# Digital.net
KiCad netlist of a schematic drawn in Altium Designer
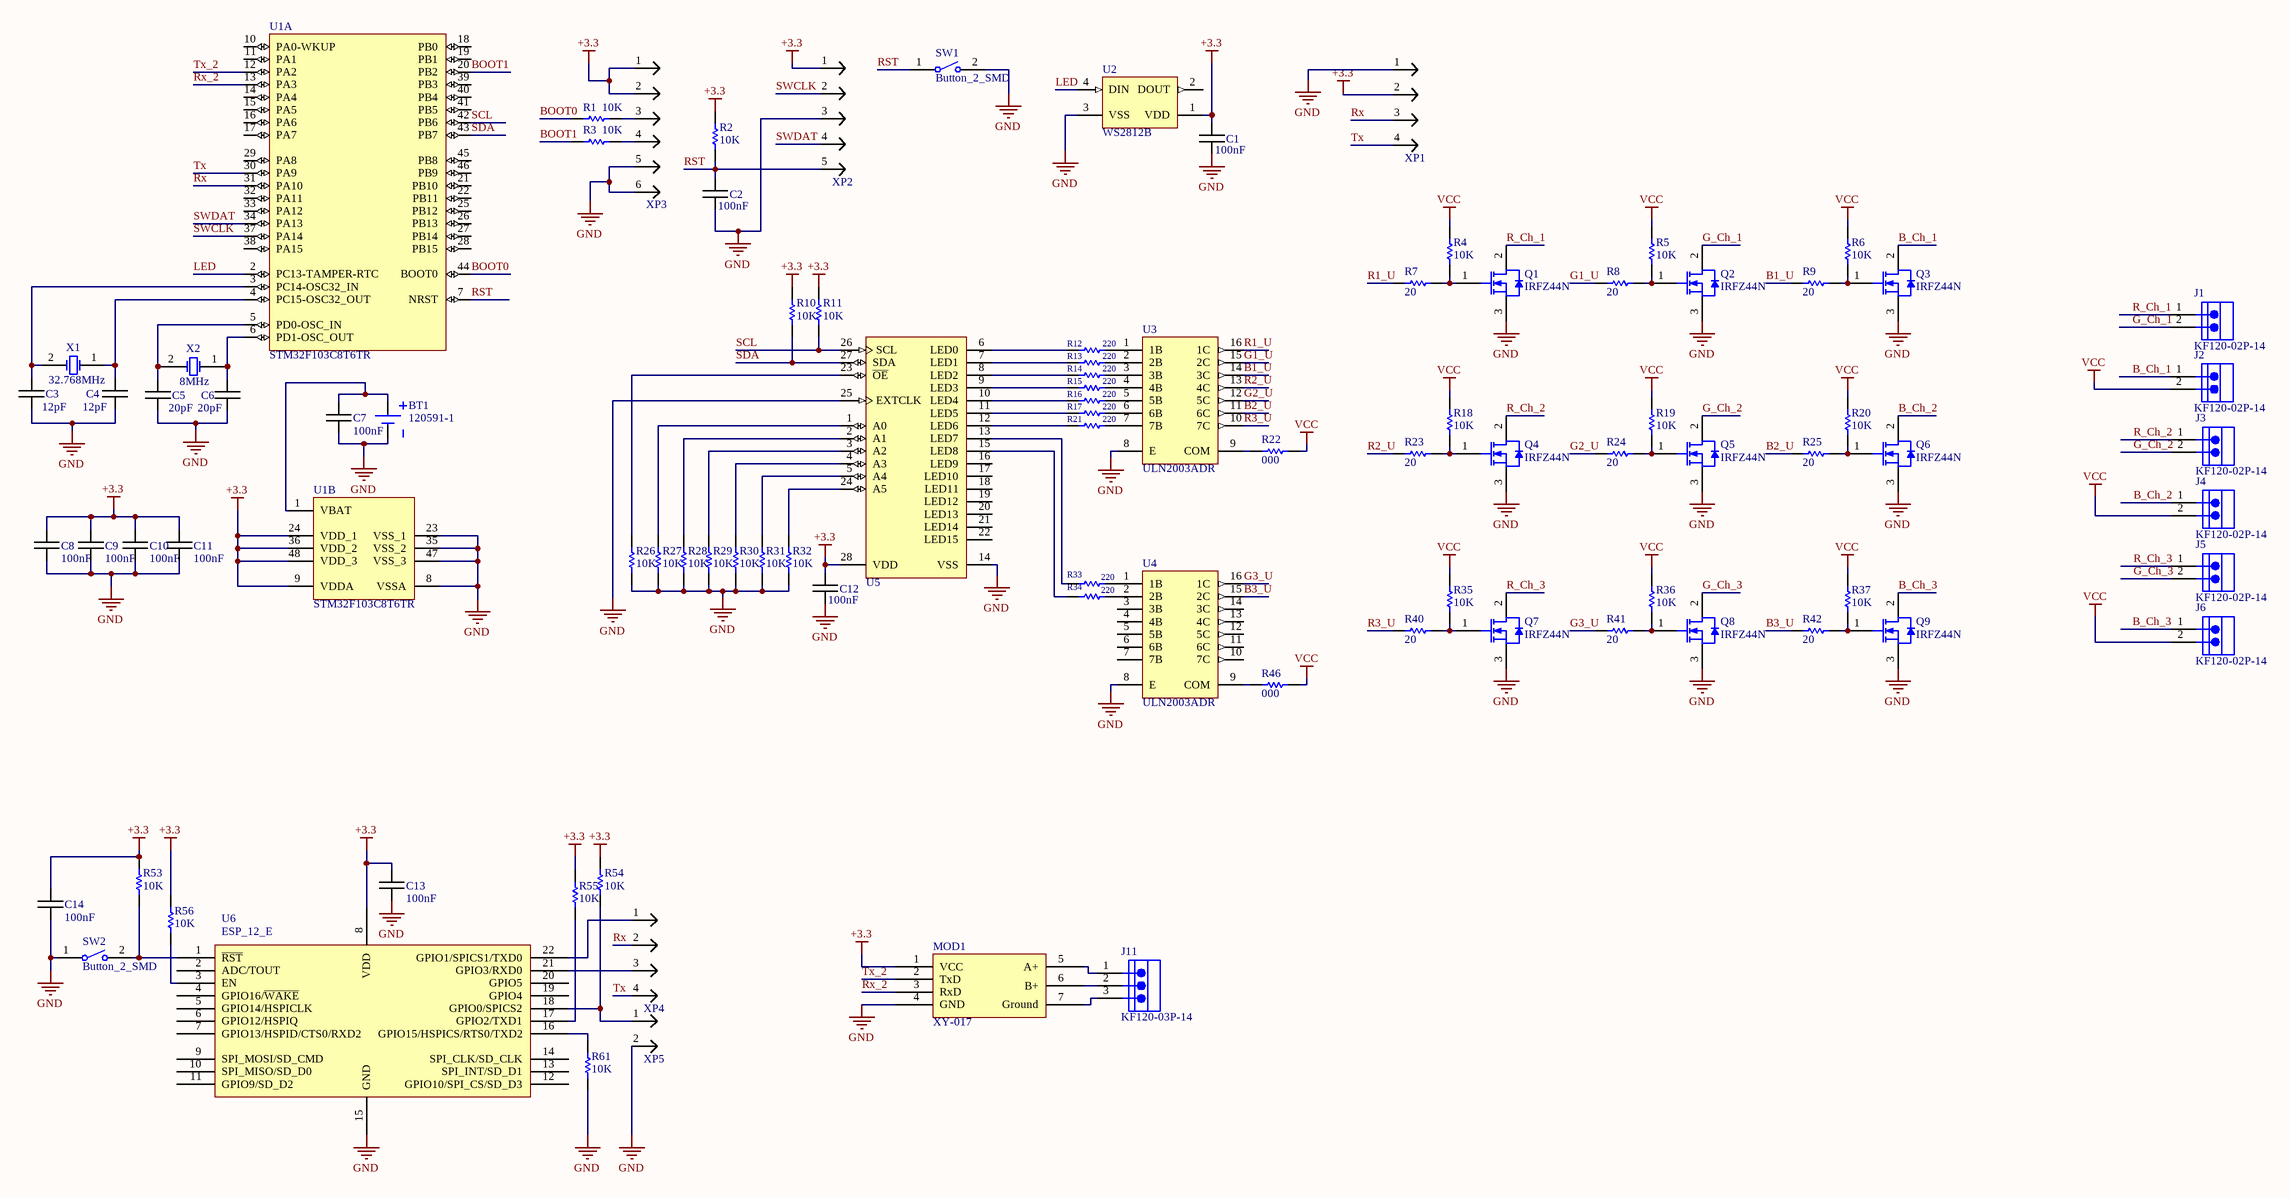
[diagram p0: Digital.SchDoc]

(export (version "E")
  (design (tool "Eeschema 10.0.6"))
  (components
    (comp (ref "BT1")
      (value "120591-1")
      (footprint "TECO-120591-1-2_V")
      (description "Lithium Battery Holder for CR2032 3V Cell")
      (fields (field (name "MANUFACTURER") "TE Connectivity"))
      (libsource (lib "altium-import") (part "root_3_CR-2032_"))
    )
    (comp (ref "C1")
      (value "CAP_SMD")
      (footprint "CAP0805")
      (description "Ceramic capacitor, 0805")
      (fields (field (name "VAL") "100nF"))
      (libsource (lib "altium-import") (part "root_1_CAP_SMD_"))
    )
    (comp (ref "C2")
      (value "CAP_SMD")
      (footprint "CAP0805")
      (description "Ceramic capacitor, 0805")
      (fields (field (name "VAL") "100nF"))
      (libsource (lib "altium-import") (part "root_1_CAP_SMD_"))
    )
    (comp (ref "C3")
      (value "CAP_SMD")
      (footprint "CAP0805")
      (description "Ceramic capacitor, 0805")
      (fields (field (name "VAL") "12pF"))
      (libsource (lib "altium-import") (part "root_1_CAP_SMD_"))
    )
    (comp (ref "C4")
      (value "CAP_SMD")
      (footprint "CAP0805")
      (description "Ceramic capacitor, 0805")
      (fields (field (name "VAL") "12pF"))
      (libsource (lib "altium-import") (part "root_1_CAP_SMD_"))
    )
    (comp (ref "C5")
      (value "CAP_SMD")
      (footprint "CAP0805")
      (description "Ceramic capacitor, 0805")
      (fields (field (name "VAL") "20pF"))
      (libsource (lib "altium-import") (part "root_1_CAP_SMD_"))
    )
    (comp (ref "C6")
      (value "CAP_SMD")
      (footprint "CAP0805")
      (description "Ceramic capacitor, 0805")
      (fields (field (name "VAL") "20pF"))
      (libsource (lib "altium-import") (part "root_1_CAP_SMD_"))
    )
    (comp (ref "C7")
      (value "CAP_SMD")
      (footprint "CAP0805")
      (description "Ceramic capacitor, 0805")
      (fields (field (name "VAL") "100nF"))
      (libsource (lib "altium-import") (part "root_1_CAP_SMD_"))
    )
    (comp (ref "C8")
      (value "CAP_SMD")
      (footprint "CAP0805")
      (description "Ceramic capacitor, 0805")
      (fields (field (name "VAL") "100nF"))
      (libsource (lib "altium-import") (part "root_1_CAP_SMD_"))
    )
    (comp (ref "C9")
      (value "CAP_SMD")
      (footprint "CAP0805")
      (description "Ceramic capacitor, 0805")
      (fields (field (name "VAL") "100nF"))
      (libsource (lib "altium-import") (part "root_1_CAP_SMD_"))
    )
    (comp (ref "C10")
      (value "CAP_SMD")
      (footprint "CAP0805")
      (description "Ceramic capacitor, 0805")
      (fields (field (name "VAL") "100nF"))
      (libsource (lib "altium-import") (part "root_1_CAP_SMD_"))
    )
    (comp (ref "C11")
      (value "CAP_SMD")
      (footprint "CAP0805")
      (description "Ceramic capacitor, 0805")
      (fields (field (name "VAL") "100nF"))
      (libsource (lib "altium-import") (part "root_1_CAP_SMD_"))
    )
    (comp (ref "C12")
      (value "CAP_SMD")
      (footprint "CAP0805")
      (description "Ceramic capacitor, 0805")
      (fields (field (name "VAL") "100nF"))
      (libsource (lib "altium-import") (part "root_1_CAP_SMD_"))
    )
    (comp (ref "C13")
      (value "CAP_SMD")
      (footprint "CAP0805")
      (description "Ceramic capacitor, 0805")
      (fields (field (name "VAL") "100nF"))
      (libsource (lib "altium-import") (part "root_1_CAP_SMD_"))
    )
    (comp (ref "C14")
      (value "CAP_SMD")
      (footprint "CAP0805")
      (description "Ceramic capacitor, 0805")
      (fields (field (name "VAL") "100nF"))
      (libsource (lib "altium-import") (part "root_1_CAP_SMD_"))
    )
    (comp (ref "J1")
      (value "KF120-02P-14")
      (footprint "KF350-3.5-02P")
      (fields (field (name "MANUFACTURER") "Cixi KaiFeng") (field (name "CONTACT") "Brass"))
      (libsource (lib "altium-import") (part "root_3_Terminal_2_"))
    )
    (comp (ref "J2")
      (value "KF120-02P-14")
      (footprint "KF350-3.5-02P")
      (fields (field (name "MANUFACTURER") "Cixi KaiFeng") (field (name "CONTACT") "Brass"))
      (libsource (lib "altium-import") (part "root_3_Terminal_2_"))
    )
    (comp (ref "J3")
      (value "KF120-02P-14")
      (footprint "KF350-3.5-02P")
      (fields (field (name "MANUFACTURER") "Cixi KaiFeng") (field (name "CONTACT") "Brass"))
      (libsource (lib "altium-import") (part "root_3_Terminal_2_"))
    )
    (comp (ref "J4")
      (value "KF120-02P-14")
      (footprint "KF350-3.5-02P")
      (fields (field (name "MANUFACTURER") "Cixi KaiFeng") (field (name "CONTACT") "Brass"))
      (libsource (lib "altium-import") (part "root_3_Terminal_2_"))
    )
    (comp (ref "J5")
      (value "KF120-02P-14")
      (footprint "KF350-3.5-02P")
      (fields (field (name "MANUFACTURER") "Cixi KaiFeng") (field (name "CONTACT") "Brass"))
      (libsource (lib "altium-import") (part "root_3_Terminal_2_"))
    )
    (comp (ref "J6")
      (value "KF120-02P-14")
      (footprint "KF350-3.5-02P")
      (fields (field (name "MANUFACTURER") "Cixi KaiFeng") (field (name "CONTACT") "Brass"))
      (libsource (lib "altium-import") (part "root_3_Terminal_2_"))
    )
    (comp (ref "J11")
      (value "KF120-03P-14")
      (footprint "KF350-3.5-03P")
      (fields (field (name "MANUFACTURER") "Cixi KaiFeng") (field (name "CONTACT") "Brass"))
      (libsource (lib "altium-import") (part "root_3_Terminal_3_"))
    )
    (comp (ref "MOD1")
      (value "XY-017")
      (footprint "XY-017")
      (description "XY-017 RS-485 to ttl module")
      (libsource (lib "altium-import") (part "root_0_XY-017_"))
    )
    (comp (ref "Q1")
      (value "IRFZ44N")
      (footprint "TO-220")
      (description "N-channel Enhancement Mode Power MOSFET 49A/55V")
      (libsource (lib "altium-import") (part "root_0_IRFZ44N_"))
    )
    (comp (ref "Q2")
      (value "IRFZ44N")
      (footprint "TO-220")
      (description "N-channel Enhancement Mode Power MOSFET 49A/55V")
      (libsource (lib "altium-import") (part "root_0_IRFZ44N_"))
    )
    (comp (ref "Q3")
      (value "IRFZ44N")
      (footprint "TO-220")
      (description "N-channel Enhancement Mode Power MOSFET 49A/55V")
      (libsource (lib "altium-import") (part "root_0_IRFZ44N_"))
    )
    (comp (ref "Q4")
      (value "IRFZ44N")
      (footprint "TO-220")
      (description "N-channel Enhancement Mode Power MOSFET 49A/55V")
      (libsource (lib "altium-import") (part "root_0_IRFZ44N_"))
    )
    (comp (ref "Q5")
      (value "IRFZ44N")
      (footprint "TO-220")
      (description "N-channel Enhancement Mode Power MOSFET 49A/55V")
      (libsource (lib "altium-import") (part "root_0_IRFZ44N_"))
    )
    (comp (ref "Q6")
      (value "IRFZ44N")
      (footprint "TO-220")
      (description "N-channel Enhancement Mode Power MOSFET 49A/55V")
      (libsource (lib "altium-import") (part "root_0_IRFZ44N_"))
    )
    (comp (ref "Q7")
      (value "IRFZ44N")
      (footprint "TO-220")
      (description "N-channel Enhancement Mode Power MOSFET 49A/55V")
      (libsource (lib "altium-import") (part "root_0_IRFZ44N_"))
    )
    (comp (ref "Q8")
      (value "IRFZ44N")
      (footprint "TO-220")
      (description "N-channel Enhancement Mode Power MOSFET 49A/55V")
      (libsource (lib "altium-import") (part "root_0_IRFZ44N_"))
    )
    (comp (ref "Q9")
      (value "IRFZ44N")
      (footprint "TO-220")
      (description "N-channel Enhancement Mode Power MOSFET 49A/55V")
      (libsource (lib "altium-import") (part "root_0_IRFZ44N_"))
    )
    (comp (ref "R1")
      (value "RES_SMD")
      (footprint "RES0805")
      (fields (field (name "VAL") "10K"))
      (libsource (lib "altium-import") (part "root_0_RES_SMD_"))
    )
    (comp (ref "R2")
      (value "RES_SMD")
      (footprint "RES0805")
      (fields (field (name "VAL") "10K"))
      (libsource (lib "altium-import") (part "root_1_RES_SMD_"))
    )
    (comp (ref "R3")
      (value "RES_SMD")
      (footprint "RES0805")
      (fields (field (name "VAL") "10K"))
      (libsource (lib "altium-import") (part "root_0_RES_SMD_"))
    )
    (comp (ref "R4")
      (value "RES_SMD")
      (footprint "RES0805")
      (fields (field (name "VAL") "10K"))
      (libsource (lib "altium-import") (part "root_1_RES_SMD_"))
    )
    (comp (ref "R5")
      (value "RES_SMD")
      (footprint "RES0805")
      (fields (field (name "VAL") "10K"))
      (libsource (lib "altium-import") (part "root_1_RES_SMD_"))
    )
    (comp (ref "R6")
      (value "RES_SMD")
      (footprint "RES0805")
      (fields (field (name "VAL") "10K"))
      (libsource (lib "altium-import") (part "root_1_RES_SMD_"))
    )
    (comp (ref "R7")
      (value "RES_SMD")
      (footprint "RES0805")
      (fields (field (name "VAL") "20"))
      (libsource (lib "altium-import") (part "root_0_RES_SMD_"))
    )
    (comp (ref "R8")
      (value "RES_SMD")
      (footprint "RES0805")
      (fields (field (name "VAL") "20"))
      (libsource (lib "altium-import") (part "root_0_RES_SMD_"))
    )
    (comp (ref "R9")
      (value "RES_SMD")
      (footprint "RES0805")
      (fields (field (name "VAL") "20"))
      (libsource (lib "altium-import") (part "root_0_RES_SMD_"))
    )
    (comp (ref "R10")
      (value "RES_SMD")
      (footprint "RES0805")
      (fields (field (name "VAL") "10K"))
      (libsource (lib "altium-import") (part "root_1_RES_SMD_"))
    )
    (comp (ref "R11")
      (value "RES_SMD")
      (footprint "RES0805")
      (fields (field (name "VAL") "10K"))
      (libsource (lib "altium-import") (part "root_1_RES_SMD_"))
    )
    (comp (ref "R12")
      (value "RES_SMD")
      (footprint "RES0805")
      (fields (field (name "VAL") "220"))
      (libsource (lib "altium-import") (part "root_2_RES_SMD_"))
    )
    (comp (ref "R13")
      (value "RES_SMD")
      (footprint "RES0805")
      (fields (field (name "VAL") "220"))
      (libsource (lib "altium-import") (part "root_2_RES_SMD_"))
    )
    (comp (ref "R14")
      (value "RES_SMD")
      (footprint "RES0805")
      (fields (field (name "VAL") "220"))
      (libsource (lib "altium-import") (part "root_2_RES_SMD_"))
    )
    (comp (ref "R15")
      (value "RES_SMD")
      (footprint "RES0805")
      (fields (field (name "VAL") "220"))
      (libsource (lib "altium-import") (part "root_2_RES_SMD_"))
    )
    (comp (ref "R16")
      (value "RES_SMD")
      (footprint "RES0805")
      (fields (field (name "VAL") "220"))
      (libsource (lib "altium-import") (part "root_2_RES_SMD_"))
    )
    (comp (ref "R17")
      (value "RES_SMD")
      (footprint "RES0805")
      (fields (field (name "VAL") "220"))
      (libsource (lib "altium-import") (part "root_2_RES_SMD_"))
    )
    (comp (ref "R18")
      (value "RES_SMD")
      (footprint "RES0805")
      (fields (field (name "VAL") "10K"))
      (libsource (lib "altium-import") (part "root_1_RES_SMD_"))
    )
    (comp (ref "R19")
      (value "RES_SMD")
      (footprint "RES0805")
      (fields (field (name "VAL") "10K"))
      (libsource (lib "altium-import") (part "root_1_RES_SMD_"))
    )
    (comp (ref "R20")
      (value "RES_SMD")
      (footprint "RES0805")
      (fields (field (name "VAL") "10K"))
      (libsource (lib "altium-import") (part "root_1_RES_SMD_"))
    )
    (comp (ref "R21")
      (value "RES_SMD")
      (footprint "RES0805")
      (fields (field (name "VAL") "220"))
      (libsource (lib "altium-import") (part "root_2_RES_SMD_"))
    )
    (comp (ref "R22")
      (value "RES_SMD")
      (footprint "RES0805")
      (fields (field (name "VAL") "000"))
      (libsource (lib "altium-import") (part "root_0_RES_SMD_"))
    )
    (comp (ref "R23")
      (value "RES_SMD")
      (footprint "RES0805")
      (fields (field (name "VAL") "20"))
      (libsource (lib "altium-import") (part "root_0_RES_SMD_"))
    )
    (comp (ref "R24")
      (value "RES_SMD")
      (footprint "RES0805")
      (fields (field (name "VAL") "20"))
      (libsource (lib "altium-import") (part "root_0_RES_SMD_"))
    )
    (comp (ref "R25")
      (value "RES_SMD")
      (footprint "RES0805")
      (fields (field (name "VAL") "20"))
      (libsource (lib "altium-import") (part "root_0_RES_SMD_"))
    )
    (comp (ref "R26")
      (value "RES_SMD")
      (footprint "RES0805")
      (fields (field (name "VAL") "10K"))
      (libsource (lib "altium-import") (part "root_1_RES_SMD_"))
    )
    (comp (ref "R27")
      (value "RES_SMD")
      (footprint "RES0805")
      (fields (field (name "VAL") "10K"))
      (libsource (lib "altium-import") (part "root_1_RES_SMD_"))
    )
    (comp (ref "R28")
      (value "RES_SMD")
      (footprint "RES0805")
      (fields (field (name "VAL") "10K"))
      (libsource (lib "altium-import") (part "root_1_RES_SMD_"))
    )
    (comp (ref "R29")
      (value "RES_SMD")
      (footprint "RES0805")
      (fields (field (name "VAL") "10K"))
      (libsource (lib "altium-import") (part "root_1_RES_SMD_"))
    )
    (comp (ref "R30")
      (value "RES_SMD")
      (footprint "RES0805")
      (fields (field (name "VAL") "10K"))
      (libsource (lib "altium-import") (part "root_1_RES_SMD_"))
    )
    (comp (ref "R31")
      (value "RES_SMD")
      (footprint "RES0805")
      (fields (field (name "VAL") "10K"))
      (libsource (lib "altium-import") (part "root_1_RES_SMD_"))
    )
    (comp (ref "R32")
      (value "RES_SMD")
      (footprint "RES0805")
      (fields (field (name "VAL") "10K"))
      (libsource (lib "altium-import") (part "root_1_RES_SMD_"))
    )
    (comp (ref "R33")
      (value "RES_SMD")
      (footprint "RES0805")
      (fields (field (name "VAL") "220"))
      (libsource (lib "altium-import") (part "root_2_RES_SMD_"))
    )
    (comp (ref "R34")
      (value "RES_SMD")
      (footprint "RES0805")
      (fields (field (name "VAL") "220"))
      (libsource (lib "altium-import") (part "root_2_RES_SMD_"))
    )
    (comp (ref "R35")
      (value "RES_SMD")
      (footprint "RES0805")
      (fields (field (name "VAL") "10K"))
      (libsource (lib "altium-import") (part "root_1_RES_SMD_"))
    )
    (comp (ref "R36")
      (value "RES_SMD")
      (footprint "RES0805")
      (fields (field (name "VAL") "10K"))
      (libsource (lib "altium-import") (part "root_1_RES_SMD_"))
    )
    (comp (ref "R37")
      (value "RES_SMD")
      (footprint "RES0805")
      (fields (field (name "VAL") "10K"))
      (libsource (lib "altium-import") (part "root_1_RES_SMD_"))
    )
    (comp (ref "R40")
      (value "RES_SMD")
      (footprint "RES0805")
      (fields (field (name "VAL") "20"))
      (libsource (lib "altium-import") (part "root_0_RES_SMD_"))
    )
    (comp (ref "R41")
      (value "RES_SMD")
      (footprint "RES0805")
      (fields (field (name "VAL") "20"))
      (libsource (lib "altium-import") (part "root_0_RES_SMD_"))
    )
    (comp (ref "R42")
      (value "RES_SMD")
      (footprint "RES0805")
      (fields (field (name "VAL") "20"))
      (libsource (lib "altium-import") (part "root_0_RES_SMD_"))
    )
    (comp (ref "R46")
      (value "RES_SMD")
      (footprint "RES0805")
      (fields (field (name "VAL") "000"))
      (libsource (lib "altium-import") (part "root_0_RES_SMD_"))
    )
    (comp (ref "R53")
      (value "RES_SMD")
      (footprint "RES0805")
      (fields (field (name "VAL") "10K"))
      (libsource (lib "altium-import") (part "root_1_RES_SMD_"))
    )
    (comp (ref "R54")
      (value "RES_SMD")
      (footprint "RES0805")
      (fields (field (name "VAL") "10K"))
      (libsource (lib "altium-import") (part "root_1_RES_SMD_"))
    )
    (comp (ref "R55")
      (value "RES_SMD")
      (footprint "RES0805")
      (fields (field (name "VAL") "10K"))
      (libsource (lib "altium-import") (part "root_1_RES_SMD_"))
    )
    (comp (ref "R56")
      (value "RES_SMD")
      (footprint "RES0805")
      (fields (field (name "VAL") "10K"))
      (libsource (lib "altium-import") (part "root_1_RES_SMD_"))
    )
    (comp (ref "R61")
      (value "RES_SMD")
      (footprint "RES0805")
      (fields (field (name "VAL") "10K"))
      (libsource (lib "altium-import") (part "root_1_RES_SMD_"))
    )
    (comp (ref "SW1")
      (value "Button_2_SMD")
      (footprint "SMD_BUT_6.3mm")
      (fields (field (name "MANUFACTURER") "TE Connectivity"))
      (libsource (lib "altium-import") (part "root_0_Button_2_SMD_"))
    )
    (comp (ref "SW2")
      (value "Button_2_SMD")
      (footprint "SMD_BUT_6.3mm")
      (fields (field (name "MANUFACTURER") "TE Connectivity"))
      (libsource (lib "altium-import") (part "root_0_Button_2_SMD_"))
    )
    (comp (ref "U1")
      (value "STM32F103C8T6TR")
      (footprint "STM-LQFP48_L")
      (libsource (lib "web.skorpio") (part "STM32F103C8T6"))
    )
    (comp (ref "U2")
      (value "WS2812B")
      (footprint "WS2812B")
      (fields (field (name "TOLERANCE") "10%"))
      (libsource (lib "altium-import") (part "root_0_WS2812B_"))
    )
    (comp (ref "U3")
      (value "ULN2003ADR")
      (footprint "SO-16_L")
      (fields (field (name "MANUFACTURER") "TexasInstruments"))
      (libsource (lib "altium-import") (part "root_0_ULN2003A_"))
    )
    (comp (ref "U4")
      (value "ULN2003ADR")
      (footprint "SO-16_L")
      (fields (field (name "MANUFACTURER") "TexasInstruments"))
      (libsource (lib "altium-import") (part "root_0_ULN2003A_"))
    )
    (comp (ref "U5")
      (value "PCA9685PW,112")
      (footprint "SOT361-1_V")
      (libsource (lib "altium-import") (part "root_0_PCA9685_"))
    )
    (comp (ref "U6")
      (value "ESP_12_E")
      (footprint "ESP_12_E")
      (description "ESP-12 Wi-Fi Module by AI-Thinker")
      (libsource (lib "altium-import") (part "root_0_ESP_12_E_"))
    )
    (comp (ref "X1")
      (value "32.768MHz")
      (footprint "Crystal_DIP - 3x8")
      (description "Low Profile Crystal")
      (fields (field (name "MANUFACTURER") "ABRACON") (field (name "TOLERANCE") "30PPM"))
      (libsource (lib "altium-import") (part "root_2_Crystal_"))
    )
    (comp (ref "X2")
      (value "8MHz")
      (footprint "Crystal_SMD")
      (description "Low Profile Crystal")
      (fields (field (name "MANUFACTURER") "ABRACON") (field (name "TOLERANCE") "30PPM"))
      (libsource (lib "altium-import") (part "root_2_Crystal_"))
    )
    (comp (ref "XP1")
      (value "PLS-04")
      (footprint "PLS-04")
      (libsource (lib "altium-import") (part "root_0_PLS-04_"))
    )
    (comp (ref "XP2")
      (value "PLS-05")
      (footprint "PLS-05")
      (libsource (lib "altium-import") (part "root_0_PLS-05_"))
    )
    (comp (ref "XP3")
      (value "PLS-03_2")
      (footprint "PLS-03_2")
      (libsource (lib "altium-import") (part "root_0_PLS-03_2_"))
    )
    (comp (ref "XP4")
      (value "PLS-02_2")
      (footprint "PLS-02_2")
      (libsource (lib "altium-import") (part "root_0_PLS-02_2_"))
    )
    (comp (ref "XP5")
      (value "PLS-02")
      (footprint "PLS-02")
      (libsource (lib "altium-import") (part "root_0_PLS-02_"))
    )
  )
  (nets
    (net (code "1") (name "+3.3") (class "Default")
      (node (ref "C1") (pin "2") (pinfunction "2_2") (pintype "passive"))
      (node (ref "C10") (pin "2") (pinfunction "2_2") (pintype "passive"))
      (node (ref "C11") (pin "2") (pinfunction "2_2") (pintype "passive"))
      (node (ref "C12") (pin "2") (pinfunction "2_2") (pintype "passive"))
      (node (ref "C13") (pin "2") (pinfunction "2_2") (pintype "passive"))
      (node (ref "C14") (pin "2") (pinfunction "2_2") (pintype "passive"))
      (node (ref "C8") (pin "2") (pinfunction "2_2") (pintype "passive"))
      (node (ref "C9") (pin "2") (pinfunction "2_2") (pintype "passive"))
      (node (ref "MOD1") (pin "1") (pinfunction "VCC_1") (pintype "passive"))
      (node (ref "R10") (pin "2") (pinfunction "2_2") (pintype "passive"))
      (node (ref "R11") (pin "2") (pinfunction "2_2") (pintype "passive"))
      (node (ref "R2") (pin "2") (pinfunction "2_2") (pintype "passive"))
      (node (ref "R53") (pin "2") (pinfunction "2_2") (pintype "passive"))
      (node (ref "R54") (pin "2") (pinfunction "2_2") (pintype "passive"))
      (node (ref "R55") (pin "2") (pinfunction "2_2") (pintype "passive"))
      (node (ref "R56") (pin "2") (pinfunction "2_2") (pintype "passive"))
      (node (ref "U1") (pin "24") (pinfunction "VDD_1_24") (pintype "power_in"))
      (node (ref "U1") (pin "36") (pinfunction "VDD_2_36") (pintype "power_in"))
      (node (ref "U1") (pin "48") (pinfunction "VDD_3_48") (pintype "power_in"))
      (node (ref "U1") (pin "9") (pinfunction "VDDA_9") (pintype "power_in"))
      (node (ref "U2") (pin "1") (pinfunction "VDD_1") (pintype "power_in"))
      (node (ref "U5") (pin "28") (pinfunction "VDD_28") (pintype "power_in"))
      (node (ref "U6") (pin "8") (pinfunction "VDD_8") (pintype "passive"))
      (node (ref "XP1") (pin "2") (pinfunction "2_2") (pintype "passive"))
      (node (ref "XP2") (pin "1") (pinfunction "1_1") (pintype "passive"))
      (node (ref "XP3") (pin "1") (pinfunction "1_1") (pintype "passive"))
      (node (ref "XP3") (pin "2") (pinfunction "2_2") (pintype "passive"))
    )
    (net (code "2") (name "/B1_U") (class "Default")
      (node (ref "R9") (pin "1") (pinfunction "1_1") (pintype "passive"))
      (node (ref "U3") (pin "14") (pinfunction "3C_14") (pintype "output"))
    )
    (net (code "3") (name "/B2_U") (class "Default")
      (node (ref "R25") (pin "1") (pinfunction "1_1") (pintype "passive"))
      (node (ref "U3") (pin "11") (pinfunction "6C_11") (pintype "output"))
    )
    (net (code "4") (name "/B3_U") (class "Default")
      (node (ref "R42") (pin "1") (pinfunction "1_1") (pintype "passive"))
      (node (ref "U4") (pin "15") (pinfunction "2C_15") (pintype "output"))
    )
    (net (code "5") (name "/BOOT0") (class "Default")
      (node (ref "R1") (pin "1") (pinfunction "1_1") (pintype "passive"))
      (node (ref "U1") (pin "44") (pinfunction "BOOT0_44") (pintype "bidirectional"))
    )
    (net (code "6") (name "/BOOT1") (class "Default")
      (node (ref "R3") (pin "1") (pinfunction "1_1") (pintype "passive"))
      (node (ref "U1") (pin "20") (pinfunction "PB2_20") (pintype "bidirectional"))
    )
    (net (code "7") (name "/B_Ch_1") (class "Default")
      (node (ref "J2") (pin "1") (pinfunction "1_1") (pintype "passive"))
      (node (ref "Q3") (pin "2") (pinfunction "D_2") (pintype "passive"))
    )
    (net (code "8") (name "/B_Ch_2") (class "Default")
      (node (ref "J4") (pin "1") (pinfunction "1_1") (pintype "passive"))
      (node (ref "Q6") (pin "2") (pinfunction "D_2") (pintype "passive"))
    )
    (net (code "9") (name "/B_Ch_3") (class "Default")
      (node (ref "J6") (pin "1") (pinfunction "1_1") (pintype "passive"))
      (node (ref "Q9") (pin "2") (pinfunction "D_2") (pintype "passive"))
    )
    (net (code "10") (name "/G1_U") (class "Default")
      (node (ref "R8") (pin "1") (pinfunction "1_1") (pintype "passive"))
      (node (ref "U3") (pin "15") (pinfunction "2C_15") (pintype "output"))
    )
    (net (code "11") (name "/G2_U") (class "Default")
      (node (ref "R24") (pin "1") (pinfunction "1_1") (pintype "passive"))
      (node (ref "U3") (pin "12") (pinfunction "5C_12") (pintype "output"))
    )
    (net (code "12") (name "/G3_U") (class "Default")
      (node (ref "R41") (pin "1") (pinfunction "1_1") (pintype "passive"))
      (node (ref "U4") (pin "16") (pinfunction "1C_16") (pintype "output"))
    )
    (net (code "13") (name "/G_Ch_1") (class "Default")
      (node (ref "J1") (pin "2") (pinfunction "2_2") (pintype "passive"))
      (node (ref "Q2") (pin "2") (pinfunction "D_2") (pintype "passive"))
    )
    (net (code "14") (name "/G_Ch_2") (class "Default")
      (node (ref "J3") (pin "2") (pinfunction "2_2") (pintype "passive"))
      (node (ref "Q5") (pin "2") (pinfunction "D_2") (pintype "passive"))
    )
    (net (code "15") (name "/G_Ch_3") (class "Default")
      (node (ref "J5") (pin "2") (pinfunction "2_2") (pintype "passive"))
      (node (ref "Q8") (pin "2") (pinfunction "D_2") (pintype "passive"))
    )
    (net (code "16") (name "/LED") (class "Default")
      (node (ref "U1") (pin "2") (pinfunction "PC13-TAMPER-RTC_2") (pintype "bidirectional"))
      (node (ref "U2") (pin "4") (pinfunction "DIN_4") (pintype "input"))
    )
    (net (code "17") (name "/R1_U") (class "Default")
      (node (ref "R7") (pin "1") (pinfunction "1_1") (pintype "passive"))
      (node (ref "U3") (pin "16") (pinfunction "1C_16") (pintype "output"))
    )
    (net (code "18") (name "/R2_U") (class "Default")
      (node (ref "R23") (pin "1") (pinfunction "1_1") (pintype "passive"))
      (node (ref "U3") (pin "13") (pinfunction "4C_13") (pintype "output"))
    )
    (net (code "19") (name "/R3_U") (class "Default")
      (node (ref "R40") (pin "1") (pinfunction "1_1") (pintype "passive"))
      (node (ref "U3") (pin "10") (pinfunction "7C_10") (pintype "output"))
    )
    (net (code "20") (name "/RST") (class "Default")
      (node (ref "C2") (pin "2") (pinfunction "2_2") (pintype "passive"))
      (node (ref "R2") (pin "1") (pinfunction "1_1") (pintype "passive"))
      (node (ref "SW1") (pin "1") (pinfunction "1_1") (pintype "passive"))
      (node (ref "U1") (pin "7") (pinfunction "NRST_7") (pintype "bidirectional"))
      (node (ref "XP2") (pin "5") (pinfunction "5_5") (pintype "passive"))
    )
    (net (code "21") (name "/R_Ch_1") (class "Default")
      (node (ref "J1") (pin "1") (pinfunction "1_1") (pintype "passive"))
      (node (ref "Q1") (pin "2") (pinfunction "D_2") (pintype "passive"))
    )
    (net (code "22") (name "/R_Ch_2") (class "Default")
      (node (ref "J3") (pin "1") (pinfunction "1_1") (pintype "passive"))
      (node (ref "Q4") (pin "2") (pinfunction "D_2") (pintype "passive"))
    )
    (net (code "23") (name "/R_Ch_3") (class "Default")
      (node (ref "J5") (pin "1") (pinfunction "1_1") (pintype "passive"))
      (node (ref "Q7") (pin "2") (pinfunction "D_2") (pintype "passive"))
    )
    (net (code "24") (name "/Rx") (class "Default")
      (node (ref "U1") (pin "31") (pinfunction "PA10_31") (pintype "bidirectional"))
      (node (ref "XP1") (pin "3") (pinfunction "3_3") (pintype "passive"))
      (node (ref "XP4") (pin "2") (pinfunction "2_2") (pintype "passive"))
    )
    (net (code "25") (name "/Rx_2") (class "Default")
      (node (ref "MOD1") (pin "3") (pinfunction "RxD_3") (pintype "passive"))
      (node (ref "U1") (pin "13") (pinfunction "PA3_13") (pintype "bidirectional"))
    )
    (net (code "26") (name "/SCL") (class "Default")
      (node (ref "R11") (pin "1") (pinfunction "1_1") (pintype "passive"))
      (node (ref "U1") (pin "42") (pinfunction "PB6_42") (pintype "bidirectional"))
      (node (ref "U5") (pin "26") (pinfunction "SCL_26") (pintype "input"))
    )
    (net (code "27") (name "/SDA") (class "Default")
      (node (ref "R10") (pin "1") (pinfunction "1_1") (pintype "passive"))
      (node (ref "U1") (pin "43") (pinfunction "PB7_43") (pintype "bidirectional"))
      (node (ref "U5") (pin "27") (pinfunction "SDA_27") (pintype "bidirectional"))
    )
    (net (code "28") (name "/SWCLK") (class "Default")
      (node (ref "U1") (pin "37") (pinfunction "PA14_37") (pintype "bidirectional"))
      (node (ref "XP2") (pin "2") (pinfunction "2_2") (pintype "passive"))
    )
    (net (code "29") (name "/SWDAT") (class "Default")
      (node (ref "U1") (pin "34") (pinfunction "PA13_34") (pintype "bidirectional"))
      (node (ref "XP2") (pin "4") (pinfunction "4_4") (pintype "passive"))
    )
    (net (code "30") (name "/Tx") (class "Default")
      (node (ref "U1") (pin "30") (pinfunction "PA9_30") (pintype "bidirectional"))
      (node (ref "XP1") (pin "4") (pinfunction "4_4") (pintype "passive"))
      (node (ref "XP4") (pin "4") (pinfunction "4_4") (pintype "passive"))
    )
    (net (code "31") (name "/Tx_2") (class "Default")
      (node (ref "MOD1") (pin "2") (pinfunction "TxD_2") (pintype "passive"))
      (node (ref "U1") (pin "12") (pinfunction "PA2_12") (pintype "bidirectional"))
    )
    (net (code "32") (name "GND") (class "Default")
      (node (ref "BT1") (pin "2") (pinfunction "-_2") (pintype "passive"))
      (node (ref "C1") (pin "1") (pinfunction "1_1") (pintype "passive"))
      (node (ref "C10") (pin "1") (pinfunction "1_1") (pintype "passive"))
      (node (ref "C11") (pin "1") (pinfunction "1_1") (pintype "passive"))
      (node (ref "C12") (pin "1") (pinfunction "1_1") (pintype "passive"))
      (node (ref "C13") (pin "1") (pinfunction "1_1") (pintype "passive"))
      (node (ref "C14") (pin "1") (pinfunction "1_1") (pintype "passive"))
      (node (ref "C2") (pin "1") (pinfunction "1_1") (pintype "passive"))
      (node (ref "C3") (pin "1") (pinfunction "1_1") (pintype "passive"))
      (node (ref "C4") (pin "1") (pinfunction "1_1") (pintype "passive"))
      (node (ref "C5") (pin "1") (pinfunction "1_1") (pintype "passive"))
      (node (ref "C6") (pin "1") (pinfunction "1_1") (pintype "passive"))
      (node (ref "C7") (pin "1") (pinfunction "1_1") (pintype "passive"))
      (node (ref "C8") (pin "1") (pinfunction "1_1") (pintype "passive"))
      (node (ref "C9") (pin "1") (pinfunction "1_1") (pintype "passive"))
      (node (ref "MOD1") (pin "4") (pinfunction "GND_4") (pintype "passive"))
      (node (ref "Q1") (pin "3") (pinfunction "S_3") (pintype "passive"))
      (node (ref "Q2") (pin "3") (pinfunction "S_3") (pintype "passive"))
      (node (ref "Q3") (pin "3") (pinfunction "S_3") (pintype "passive"))
      (node (ref "Q4") (pin "3") (pinfunction "S_3") (pintype "passive"))
      (node (ref "Q5") (pin "3") (pinfunction "S_3") (pintype "passive"))
      (node (ref "Q6") (pin "3") (pinfunction "S_3") (pintype "passive"))
      (node (ref "Q7") (pin "3") (pinfunction "S_3") (pintype "passive"))
      (node (ref "Q8") (pin "3") (pinfunction "S_3") (pintype "passive"))
      (node (ref "Q9") (pin "3") (pinfunction "S_3") (pintype "passive"))
      (node (ref "R26") (pin "1") (pinfunction "1_1") (pintype "passive"))
      (node (ref "R27") (pin "1") (pinfunction "1_1") (pintype "passive"))
      (node (ref "R28") (pin "1") (pinfunction "1_1") (pintype "passive"))
      (node (ref "R29") (pin "1") (pinfunction "1_1") (pintype "passive"))
      (node (ref "R30") (pin "1") (pinfunction "1_1") (pintype "passive"))
      (node (ref "R31") (pin "1") (pinfunction "1_1") (pintype "passive"))
      (node (ref "R32") (pin "1") (pinfunction "1_1") (pintype "passive"))
      (node (ref "R61") (pin "1") (pinfunction "1_1") (pintype "passive"))
      (node (ref "SW1") (pin "2") (pinfunction "2_2") (pintype "passive"))
      (node (ref "SW2") (pin "1") (pinfunction "1_1") (pintype "passive"))
      (node (ref "U1") (pin "23") (pinfunction "VSS_1_23") (pintype "power_in"))
      (node (ref "U1") (pin "35") (pinfunction "VSS_2_35") (pintype "power_in"))
      (node (ref "U1") (pin "47") (pinfunction "VSS_3_47") (pintype "power_in"))
      (node (ref "U1") (pin "8") (pinfunction "VSSA_8") (pintype "power_in"))
      (node (ref "U2") (pin "3") (pinfunction "VSS_3") (pintype "power_in"))
      (node (ref "U3") (pin "8") (pinfunction "E_8") (pintype "passive"))
      (node (ref "U4") (pin "8") (pinfunction "E_8") (pintype "passive"))
      (node (ref "U5") (pin "14") (pinfunction "VSS_14") (pintype "power_in"))
      (node (ref "U5") (pin "25") (pinfunction "EXTCLK_25") (pintype "input"))
      (node (ref "U6") (pin "15") (pinfunction "GND_15") (pintype "passive"))
      (node (ref "XP1") (pin "1") (pinfunction "1_1") (pintype "passive"))
      (node (ref "XP2") (pin "3") (pinfunction "3_3") (pintype "passive"))
      (node (ref "XP3") (pin "5") (pinfunction "5_5") (pintype "passive"))
      (node (ref "XP3") (pin "6") (pinfunction "6_6") (pintype "passive"))
      (node (ref "XP5") (pin "2") (pinfunction "2_2") (pintype "passive"))
    )
    (net (code "33") (name "Net-(BT1-+)") (class "Default")
      (node (ref "BT1") (pin "1") (pinfunction "+_1") (pintype "passive"))
      (node (ref "C7") (pin "2") (pinfunction "2_2") (pintype "passive"))
      (node (ref "U1") (pin "1") (pinfunction "VBAT_1") (pintype "power_in"))
    )
    (net (code "34") (name "Net-(MOD1-A+)") (class "Default")
      (node (ref "J11") (pin "1") (pinfunction "1_1") (pintype "passive"))
      (node (ref "MOD1") (pin "5") (pinfunction "A+_5") (pintype "passive"))
    )
    (net (code "35") (name "Net-(MOD1-B+)") (class "Default")
      (node (ref "J11") (pin "2") (pinfunction "2_2") (pintype "passive"))
      (node (ref "MOD1") (pin "6") (pinfunction "B+_6") (pintype "passive"))
    )
    (net (code "36") (name "Net-(MOD1-Ground)") (class "Default")
      (node (ref "J11") (pin "3") (pinfunction "3_3") (pintype "passive"))
      (node (ref "MOD1") (pin "7") (pinfunction "Ground_7") (pintype "passive"))
    )
    (net (code "37") (name "Net-(Q1-G)") (class "Default")
      (node (ref "Q1") (pin "1") (pinfunction "G_1") (pintype "passive"))
      (node (ref "R4") (pin "1") (pinfunction "1_1") (pintype "passive"))
      (node (ref "R7") (pin "2") (pinfunction "2_2") (pintype "passive"))
    )
    (net (code "38") (name "Net-(Q2-G)") (class "Default")
      (node (ref "Q2") (pin "1") (pinfunction "G_1") (pintype "passive"))
      (node (ref "R5") (pin "1") (pinfunction "1_1") (pintype "passive"))
      (node (ref "R8") (pin "2") (pinfunction "2_2") (pintype "passive"))
    )
    (net (code "39") (name "Net-(Q3-G)") (class "Default")
      (node (ref "Q3") (pin "1") (pinfunction "G_1") (pintype "passive"))
      (node (ref "R6") (pin "1") (pinfunction "1_1") (pintype "passive"))
      (node (ref "R9") (pin "2") (pinfunction "2_2") (pintype "passive"))
    )
    (net (code "40") (name "Net-(Q4-G)") (class "Default")
      (node (ref "Q4") (pin "1") (pinfunction "G_1") (pintype "passive"))
      (node (ref "R18") (pin "1") (pinfunction "1_1") (pintype "passive"))
      (node (ref "R23") (pin "2") (pinfunction "2_2") (pintype "passive"))
    )
    (net (code "41") (name "Net-(Q5-G)") (class "Default")
      (node (ref "Q5") (pin "1") (pinfunction "G_1") (pintype "passive"))
      (node (ref "R19") (pin "1") (pinfunction "1_1") (pintype "passive"))
      (node (ref "R24") (pin "2") (pinfunction "2_2") (pintype "passive"))
    )
    (net (code "42") (name "Net-(Q6-G)") (class "Default")
      (node (ref "Q6") (pin "1") (pinfunction "G_1") (pintype "passive"))
      (node (ref "R20") (pin "1") (pinfunction "1_1") (pintype "passive"))
      (node (ref "R25") (pin "2") (pinfunction "2_2") (pintype "passive"))
    )
    (net (code "43") (name "Net-(Q7-G)") (class "Default")
      (node (ref "Q7") (pin "1") (pinfunction "G_1") (pintype "passive"))
      (node (ref "R35") (pin "1") (pinfunction "1_1") (pintype "passive"))
      (node (ref "R40") (pin "2") (pinfunction "2_2") (pintype "passive"))
    )
    (net (code "44") (name "Net-(Q8-G)") (class "Default")
      (node (ref "Q8") (pin "1") (pinfunction "G_1") (pintype "passive"))
      (node (ref "R36") (pin "1") (pinfunction "1_1") (pintype "passive"))
      (node (ref "R41") (pin "2") (pinfunction "2_2") (pintype "passive"))
    )
    (net (code "45") (name "Net-(Q9-G)") (class "Default")
      (node (ref "Q9") (pin "1") (pinfunction "G_1") (pintype "passive"))
      (node (ref "R37") (pin "1") (pinfunction "1_1") (pintype "passive"))
      (node (ref "R42") (pin "2") (pinfunction "2_2") (pintype "passive"))
    )
    (net (code "46") (name "Net-(R1-Pad2)") (class "Default")
      (node (ref "R1") (pin "2") (pinfunction "2_2") (pintype "passive"))
      (node (ref "XP3") (pin "3") (pinfunction "3_3") (pintype "passive"))
    )
    (net (code "47") (name "Net-(R3-Pad2)") (class "Default")
      (node (ref "R3") (pin "2") (pinfunction "2_2") (pintype "passive"))
      (node (ref "XP3") (pin "4") (pinfunction "4_4") (pintype "passive"))
    )
    (net (code "48") (name "Net-(U1A-PC14-OSC32_IN)") (class "Default")
      (node (ref "C3") (pin "2") (pinfunction "2_2") (pintype "passive"))
      (node (ref "U1") (pin "3") (pinfunction "PC14-OSC32_IN_3") (pintype "bidirectional"))
      (node (ref "X1") (pin "2") (pinfunction "X2_2") (pintype "passive"))
    )
    (net (code "49") (name "Net-(U1A-PC15-OSC32_OUT)") (class "Default")
      (node (ref "C4") (pin "2") (pinfunction "2_2") (pintype "passive"))
      (node (ref "U1") (pin "4") (pinfunction "PC15-OSC32_OUT_4") (pintype "bidirectional"))
      (node (ref "X1") (pin "1") (pinfunction "X1_1") (pintype "passive"))
    )
    (net (code "50") (name "Net-(U1A-PD0-OSC_IN)") (class "Default")
      (node (ref "C5") (pin "2") (pinfunction "2_2") (pintype "passive"))
      (node (ref "U1") (pin "5") (pinfunction "PD0-OSC_IN_5") (pintype "bidirectional"))
      (node (ref "X2") (pin "2") (pinfunction "X2_2") (pintype "passive"))
    )
    (net (code "51") (name "Net-(U1A-PD1-OSC_OUT)") (class "Default")
      (node (ref "C6") (pin "2") (pinfunction "2_2") (pintype "passive"))
      (node (ref "U1") (pin "6") (pinfunction "PD1-OSC_OUT_6") (pintype "bidirectional"))
      (node (ref "X2") (pin "1") (pinfunction "X1_1") (pintype "passive"))
    )
    (net (code "52") (name "Net-(U3-1B)") (class "Default")
      (node (ref "R12") (pin "1") (pinfunction "1_1") (pintype "passive"))
      (node (ref "U3") (pin "1") (pinfunction "1B_1") (pintype "passive"))
    )
    (net (code "53") (name "Net-(U3-2B)") (class "Default")
      (node (ref "R13") (pin "1") (pinfunction "1_1") (pintype "passive"))
      (node (ref "U3") (pin "2") (pinfunction "2B_2") (pintype "passive"))
    )
    (net (code "54") (name "Net-(U3-3B)") (class "Default")
      (node (ref "R14") (pin "1") (pinfunction "1_1") (pintype "passive"))
      (node (ref "U3") (pin "3") (pinfunction "3B_3") (pintype "passive"))
    )
    (net (code "55") (name "Net-(U3-4B)") (class "Default")
      (node (ref "R15") (pin "1") (pinfunction "1_1") (pintype "passive"))
      (node (ref "U3") (pin "4") (pinfunction "4B_4") (pintype "passive"))
    )
    (net (code "56") (name "Net-(U3-5B)") (class "Default")
      (node (ref "R16") (pin "1") (pinfunction "1_1") (pintype "passive"))
      (node (ref "U3") (pin "5") (pinfunction "5B_5") (pintype "passive"))
    )
    (net (code "57") (name "Net-(U3-6B)") (class "Default")
      (node (ref "R17") (pin "1") (pinfunction "1_1") (pintype "passive"))
      (node (ref "U3") (pin "6") (pinfunction "6B_6") (pintype "passive"))
    )
    (net (code "58") (name "Net-(U3-7B)") (class "Default")
      (node (ref "R21") (pin "1") (pinfunction "1_1") (pintype "passive"))
      (node (ref "U3") (pin "7") (pinfunction "7B_7") (pintype "passive"))
    )
    (net (code "59") (name "Net-(U3-COM)") (class "Default")
      (node (ref "R22") (pin "1") (pinfunction "1_1") (pintype "passive"))
      (node (ref "U3") (pin "9") (pinfunction "COM_9") (pintype "passive"))
    )
    (net (code "60") (name "Net-(U4-1B)") (class "Default")
      (node (ref "R33") (pin "1") (pinfunction "1_1") (pintype "passive"))
      (node (ref "U4") (pin "1") (pinfunction "1B_1") (pintype "passive"))
    )
    (net (code "61") (name "Net-(U4-2B)") (class "Default")
      (node (ref "R34") (pin "1") (pinfunction "1_1") (pintype "passive"))
      (node (ref "U4") (pin "2") (pinfunction "2B_2") (pintype "passive"))
    )
    (net (code "62") (name "Net-(U4-COM)") (class "Default")
      (node (ref "R46") (pin "1") (pinfunction "1_1") (pintype "passive"))
      (node (ref "U4") (pin "9") (pinfunction "COM_9") (pintype "passive"))
    )
    (net (code "63") (name "Net-(U5-A0)") (class "Default")
      (node (ref "R27") (pin "2") (pinfunction "2_2") (pintype "passive"))
      (node (ref "U5") (pin "1") (pinfunction "A0_1") (pintype "bidirectional"))
    )
    (net (code "64") (name "Net-(U5-A1)") (class "Default")
      (node (ref "R28") (pin "2") (pinfunction "2_2") (pintype "passive"))
      (node (ref "U5") (pin "2") (pinfunction "A1_2") (pintype "bidirectional"))
    )
    (net (code "65") (name "Net-(U5-A2)") (class "Default")
      (node (ref "R29") (pin "2") (pinfunction "2_2") (pintype "passive"))
      (node (ref "U5") (pin "3") (pinfunction "A2_3") (pintype "bidirectional"))
    )
    (net (code "66") (name "Net-(U5-A3)") (class "Default")
      (node (ref "R30") (pin "2") (pinfunction "2_2") (pintype "passive"))
      (node (ref "U5") (pin "4") (pinfunction "A3_4") (pintype "bidirectional"))
    )
    (net (code "67") (name "Net-(U5-A4)") (class "Default")
      (node (ref "R31") (pin "2") (pinfunction "2_2") (pintype "passive"))
      (node (ref "U5") (pin "5") (pinfunction "A4_5") (pintype "bidirectional"))
    )
    (net (code "68") (name "Net-(U5-A5)") (class "Default")
      (node (ref "R32") (pin "2") (pinfunction "2_2") (pintype "passive"))
      (node (ref "U5") (pin "24") (pinfunction "A5_24") (pintype "bidirectional"))
    )
    (net (code "69") (name "Net-(U5-LED0)") (class "Default")
      (node (ref "R12") (pin "2") (pinfunction "2_2") (pintype "passive"))
      (node (ref "U5") (pin "6") (pinfunction "LED0_6") (pintype "tri_state"))
    )
    (net (code "70") (name "Net-(U5-LED1)") (class "Default")
      (node (ref "R13") (pin "2") (pinfunction "2_2") (pintype "passive"))
      (node (ref "U5") (pin "7") (pinfunction "LED1_7") (pintype "tri_state"))
    )
    (net (code "71") (name "Net-(U5-LED2)") (class "Default")
      (node (ref "R14") (pin "2") (pinfunction "2_2") (pintype "passive"))
      (node (ref "U5") (pin "8") (pinfunction "LED2_8") (pintype "tri_state"))
    )
    (net (code "72") (name "Net-(U5-LED3)") (class "Default")
      (node (ref "R15") (pin "2") (pinfunction "2_2") (pintype "passive"))
      (node (ref "U5") (pin "9") (pinfunction "LED3_9") (pintype "tri_state"))
    )
    (net (code "73") (name "Net-(U5-LED4)") (class "Default")
      (node (ref "R16") (pin "2") (pinfunction "2_2") (pintype "passive"))
      (node (ref "U5") (pin "10") (pinfunction "LED4_10") (pintype "tri_state"))
    )
    (net (code "74") (name "Net-(U5-LED5)") (class "Default")
      (node (ref "R17") (pin "2") (pinfunction "2_2") (pintype "passive"))
      (node (ref "U5") (pin "11") (pinfunction "LED5_11") (pintype "tri_state"))
    )
    (net (code "75") (name "Net-(U5-LED6)") (class "Default")
      (node (ref "R21") (pin "2") (pinfunction "2_2") (pintype "passive"))
      (node (ref "U5") (pin "12") (pinfunction "LED6_12") (pintype "tri_state"))
    )
    (net (code "76") (name "Net-(U5-LED7)") (class "Default")
      (node (ref "R33") (pin "2") (pinfunction "2_2") (pintype "passive"))
      (node (ref "U5") (pin "13") (pinfunction "LED7_13") (pintype "tri_state"))
    )
    (net (code "77") (name "Net-(U5-LED8)") (class "Default")
      (node (ref "R34") (pin "2") (pinfunction "2_2") (pintype "passive"))
      (node (ref "U5") (pin "15") (pinfunction "LED8_15") (pintype "tri_state"))
    )
    (net (code "78") (name "Net-(U5-~{OE})") (class "Default")
      (node (ref "R26") (pin "2") (pinfunction "2_2") (pintype "passive"))
      (node (ref "U5") (pin "23") (pinfunction "~{OE}_23") (pintype "bidirectional"))
    )
    (net (code "79") (name "Net-(U6-EN)") (class "Default")
      (node (ref "R56") (pin "1") (pinfunction "1_1") (pintype "passive"))
      (node (ref "U6") (pin "3") (pinfunction "EN_3") (pintype "passive"))
    )
    (net (code "80") (name "Net-(U6-GPIO0{slash}SPICS2)") (class "Default")
      (node (ref "R54") (pin "1") (pinfunction "1_1") (pintype "passive"))
      (node (ref "U6") (pin "18") (pinfunction "GPIO0/SPICS2_18") (pintype "passive"))
      (node (ref "XP5") (pin "1") (pinfunction "1_1") (pintype "passive"))
    )
    (net (code "81") (name "Net-(U6-GPIO1{slash}SPICS1{slash}TXD0)") (class "Default")
      (node (ref "U6") (pin "22") (pinfunction "GPIO1/SPICS1/TXD0_22") (pintype "passive"))
      (node (ref "XP4") (pin "1") (pinfunction "1_1") (pintype "passive"))
    )
    (net (code "82") (name "Net-(U6-GPIO2{slash}TXD1)") (class "Default")
      (node (ref "R55") (pin "1") (pinfunction "1_1") (pintype "passive"))
      (node (ref "U6") (pin "17") (pinfunction "GPIO2/TXD1_17") (pintype "passive"))
    )
    (net (code "83") (name "Net-(U6-GPIO3{slash}RXD0)") (class "Default")
      (node (ref "U6") (pin "21") (pinfunction "GPIO3/RXD0_21") (pintype "passive"))
      (node (ref "XP4") (pin "3") (pinfunction "3_3") (pintype "passive"))
    )
    (net (code "84") (name "Net-(U6-GPIO15{slash}HSPICS{slash}RTS0{slash}TXD2)") (class "Default")
      (node (ref "R61") (pin "2") (pinfunction "2_2") (pintype "passive"))
      (node (ref "U6") (pin "16") (pinfunction "GPIO15/HSPICS/RTS0/TXD2_16") (pintype "passive"))
    )
    (net (code "85") (name "Net-(U6-~{RST})") (class "Default")
      (node (ref "R53") (pin "1") (pinfunction "1_1") (pintype "passive"))
      (node (ref "SW2") (pin "2") (pinfunction "2_2") (pintype "passive"))
      (node (ref "U6") (pin "1") (pinfunction "~{RST}_1") (pintype "passive"))
    )
    (net (code "86") (name "VCC") (class "Default")
      (node (ref "J2") (pin "2") (pinfunction "2_2") (pintype "passive"))
      (node (ref "J4") (pin "2") (pinfunction "2_2") (pintype "passive"))
      (node (ref "J6") (pin "2") (pinfunction "2_2") (pintype "passive"))
      (node (ref "R18") (pin "2") (pinfunction "2_2") (pintype "passive"))
      (node (ref "R19") (pin "2") (pinfunction "2_2") (pintype "passive"))
      (node (ref "R20") (pin "2") (pinfunction "2_2") (pintype "passive"))
      (node (ref "R22") (pin "2") (pinfunction "2_2") (pintype "passive"))
      (node (ref "R35") (pin "2") (pinfunction "2_2") (pintype "passive"))
      (node (ref "R36") (pin "2") (pinfunction "2_2") (pintype "passive"))
      (node (ref "R37") (pin "2") (pinfunction "2_2") (pintype "passive"))
      (node (ref "R4") (pin "2") (pinfunction "2_2") (pintype "passive"))
      (node (ref "R46") (pin "2") (pinfunction "2_2") (pintype "passive"))
      (node (ref "R5") (pin "2") (pinfunction "2_2") (pintype "passive"))
      (node (ref "R6") (pin "2") (pinfunction "2_2") (pintype "passive"))
    )
    (net (code "87") (name "unconnected-(U1A-PA0-WKUP-Pad10)") (class "Default")
      (node (ref "U1") (pin "10") (pinfunction "PA0-WKUP_10") (pintype "bidirectional"))
    )
    (net (code "88") (name "unconnected-(U1A-PA1-Pad11)") (class "Default")
      (node (ref "U1") (pin "11") (pinfunction "PA1_11") (pintype "bidirectional"))
    )
    (net (code "89") (name "unconnected-(U1A-PA4-Pad14)") (class "Default")
      (node (ref "U1") (pin "14") (pinfunction "PA4_14") (pintype "bidirectional"))
    )
    (net (code "90") (name "unconnected-(U1A-PA5-Pad15)") (class "Default")
      (node (ref "U1") (pin "15") (pinfunction "PA5_15") (pintype "bidirectional"))
    )
    (net (code "91") (name "unconnected-(U1A-PA6-Pad16)") (class "Default")
      (node (ref "U1") (pin "16") (pinfunction "PA6_16") (pintype "bidirectional"))
    )
    (net (code "92") (name "unconnected-(U1A-PA7-Pad17)") (class "Default")
      (node (ref "U1") (pin "17") (pinfunction "PA7_17") (pintype "bidirectional"))
    )
    (net (code "93") (name "unconnected-(U1A-PA8-Pad29)") (class "Default")
      (node (ref "U1") (pin "29") (pinfunction "PA8_29") (pintype "bidirectional"))
    )
    (net (code "94") (name "unconnected-(U1A-PA11-Pad32)") (class "Default")
      (node (ref "U1") (pin "32") (pinfunction "PA11_32") (pintype "bidirectional"))
    )
    (net (code "95") (name "unconnected-(U1A-PA12-Pad33)") (class "Default")
      (node (ref "U1") (pin "33") (pinfunction "PA12_33") (pintype "bidirectional"))
    )
    (net (code "96") (name "unconnected-(U1A-PA15-Pad38)") (class "Default")
      (node (ref "U1") (pin "38") (pinfunction "PA15_38") (pintype "bidirectional"))
    )
    (net (code "97") (name "unconnected-(U1A-PB0-Pad18)") (class "Default")
      (node (ref "U1") (pin "18") (pinfunction "PB0_18") (pintype "bidirectional"))
    )
    (net (code "98") (name "unconnected-(U1A-PB1-Pad19)") (class "Default")
      (node (ref "U1") (pin "19") (pinfunction "PB1_19") (pintype "bidirectional"))
    )
    (net (code "99") (name "unconnected-(U1A-PB3-Pad39)") (class "Default")
      (node (ref "U1") (pin "39") (pinfunction "PB3_39") (pintype "bidirectional"))
    )
    (net (code "100") (name "unconnected-(U1A-PB4-Pad40)") (class "Default")
      (node (ref "U1") (pin "40") (pinfunction "PB4_40") (pintype "bidirectional"))
    )
    (net (code "101") (name "unconnected-(U1A-PB5-Pad41)") (class "Default")
      (node (ref "U1") (pin "41") (pinfunction "PB5_41") (pintype "bidirectional"))
    )
    (net (code "102") (name "unconnected-(U1A-PB8-Pad45)") (class "Default")
      (node (ref "U1") (pin "45") (pinfunction "PB8_45") (pintype "bidirectional"))
    )
    (net (code "103") (name "unconnected-(U1A-PB9-Pad46)") (class "Default")
      (node (ref "U1") (pin "46") (pinfunction "PB9_46") (pintype "bidirectional"))
    )
    (net (code "104") (name "unconnected-(U1A-PB10-Pad21)") (class "Default")
      (node (ref "U1") (pin "21") (pinfunction "PB10_21") (pintype "bidirectional"))
    )
    (net (code "105") (name "unconnected-(U1A-PB11-Pad22)") (class "Default")
      (node (ref "U1") (pin "22") (pinfunction "PB11_22") (pintype "bidirectional"))
    )
    (net (code "106") (name "unconnected-(U1A-PB12-Pad25)") (class "Default")
      (node (ref "U1") (pin "25") (pinfunction "PB12_25") (pintype "bidirectional"))
    )
    (net (code "107") (name "unconnected-(U1A-PB13-Pad26)") (class "Default")
      (node (ref "U1") (pin "26") (pinfunction "PB13_26") (pintype "bidirectional"))
    )
    (net (code "108") (name "unconnected-(U1A-PB14-Pad27)") (class "Default")
      (node (ref "U1") (pin "27") (pinfunction "PB14_27") (pintype "bidirectional"))
    )
    (net (code "109") (name "unconnected-(U1A-PB15-Pad28)") (class "Default")
      (node (ref "U1") (pin "28") (pinfunction "PB15_28") (pintype "bidirectional"))
    )
    (net (code "110") (name "unconnected-(U2-DOUT-Pad2)") (class "Default")
      (node (ref "U2") (pin "2") (pinfunction "DOUT_2") (pintype "output"))
    )
    (net (code "111") (name "unconnected-(U4-3B-Pad3)") (class "Default")
      (node (ref "U4") (pin "3") (pinfunction "3B_3") (pintype "passive"))
    )
    (net (code "112") (name "unconnected-(U4-3C-Pad14)") (class "Default")
      (node (ref "U4") (pin "14") (pinfunction "3C_14") (pintype "output"))
    )
    (net (code "113") (name "unconnected-(U4-4B-Pad4)") (class "Default")
      (node (ref "U4") (pin "4") (pinfunction "4B_4") (pintype "passive"))
    )
    (net (code "114") (name "unconnected-(U4-4C-Pad13)") (class "Default")
      (node (ref "U4") (pin "13") (pinfunction "4C_13") (pintype "output"))
    )
    (net (code "115") (name "unconnected-(U4-5B-Pad5)") (class "Default")
      (node (ref "U4") (pin "5") (pinfunction "5B_5") (pintype "passive"))
    )
    (net (code "116") (name "unconnected-(U4-5C-Pad12)") (class "Default")
      (node (ref "U4") (pin "12") (pinfunction "5C_12") (pintype "output"))
    )
    (net (code "117") (name "unconnected-(U4-6B-Pad6)") (class "Default")
      (node (ref "U4") (pin "6") (pinfunction "6B_6") (pintype "passive"))
    )
    (net (code "118") (name "unconnected-(U4-6C-Pad11)") (class "Default")
      (node (ref "U4") (pin "11") (pinfunction "6C_11") (pintype "output"))
    )
    (net (code "119") (name "unconnected-(U4-7B-Pad7)") (class "Default")
      (node (ref "U4") (pin "7") (pinfunction "7B_7") (pintype "passive"))
    )
    (net (code "120") (name "unconnected-(U4-7C-Pad10)") (class "Default")
      (node (ref "U4") (pin "10") (pinfunction "7C_10") (pintype "output"))
    )
    (net (code "121") (name "unconnected-(U5-LED9-Pad16)") (class "Default")
      (node (ref "U5") (pin "16") (pinfunction "LED9_16") (pintype "tri_state"))
    )
    (net (code "122") (name "unconnected-(U5-LED10-Pad17)") (class "Default")
      (node (ref "U5") (pin "17") (pinfunction "LED10_17") (pintype "tri_state"))
    )
    (net (code "123") (name "unconnected-(U5-LED11-Pad18)") (class "Default")
      (node (ref "U5") (pin "18") (pinfunction "LED11_18") (pintype "tri_state"))
    )
    (net (code "124") (name "unconnected-(U5-LED12-Pad19)") (class "Default")
      (node (ref "U5") (pin "19") (pinfunction "LED12_19") (pintype "tri_state"))
    )
    (net (code "125") (name "unconnected-(U5-LED13-Pad20)") (class "Default")
      (node (ref "U5") (pin "20") (pinfunction "LED13_20") (pintype "tri_state"))
    )
    (net (code "126") (name "unconnected-(U5-LED14-Pad21)") (class "Default")
      (node (ref "U5") (pin "21") (pinfunction "LED14_21") (pintype "tri_state"))
    )
    (net (code "127") (name "unconnected-(U5-LED15-Pad22)") (class "Default")
      (node (ref "U5") (pin "22") (pinfunction "LED15_22") (pintype "tri_state"))
    )
    (net (code "128") (name "unconnected-(U6-ADC{slash}TOUT-Pad2)") (class "Default")
      (node (ref "U6") (pin "2") (pinfunction "ADC/TOUT_2") (pintype "passive"))
    )
    (net (code "129") (name "unconnected-(U6-GPIO4-Pad19)") (class "Default")
      (node (ref "U6") (pin "19") (pinfunction "GPIO4_19") (pintype "passive"))
    )
    (net (code "130") (name "unconnected-(U6-GPIO5-Pad20)") (class "Default")
      (node (ref "U6") (pin "20") (pinfunction "GPIO5_20") (pintype "passive"))
    )
    (net (code "131") (name "unconnected-(U6-GPIO9{slash}SD_D2-Pad11)") (class "Default")
      (node (ref "U6") (pin "11") (pinfunction "GPIO9/SD_D2_11") (pintype "passive"))
    )
    (net (code "132") (name "unconnected-(U6-GPIO10{slash}SPI_CS{slash}SD_D3-Pad12)") (class "Default")
      (node (ref "U6") (pin "12") (pinfunction "GPIO10/SPI_CS/SD_D3_12") (pintype "passive"))
    )
    (net (code "133") (name "unconnected-(U6-GPIO12{slash}HSPIQ-Pad6)") (class "Default")
      (node (ref "U6") (pin "6") (pinfunction "GPIO12/HSPIQ_6") (pintype "passive"))
    )
    (net (code "134") (name "unconnected-(U6-GPIO13{slash}HSPID{slash}CTS0{slash}RXD2-Pad7)") (class "Default")
      (node (ref "U6") (pin "7") (pinfunction "GPIO13/HSPID/CTS0/RXD2_7") (pintype "passive"))
    )
    (net (code "135") (name "unconnected-(U6-GPIO14{slash}HSPICLK-Pad5)") (class "Default")
      (node (ref "U6") (pin "5") (pinfunction "GPIO14/HSPICLK_5") (pintype "passive"))
    )
    (net (code "136") (name "unconnected-(U6-GPIO16{slash}~{WAKE}-Pad4)") (class "Default")
      (node (ref "U6") (pin "4") (pinfunction "GPIO16/~{WAKE}_4") (pintype "passive"))
    )
    (net (code "137") (name "unconnected-(U6-SPI_CLK{slash}SD_CLK-Pad14)") (class "Default")
      (node (ref "U6") (pin "14") (pinfunction "SPI_CLK/SD_CLK_14") (pintype "passive"))
    )
    (net (code "138") (name "unconnected-(U6-SPI_INT{slash}SD_D1-Pad13)") (class "Default")
      (node (ref "U6") (pin "13") (pinfunction "SPI_INT/SD_D1_13") (pintype "passive"))
    )
    (net (code "139") (name "unconnected-(U6-SPI_MISO{slash}SD_D0-Pad10)") (class "Default")
      (node (ref "U6") (pin "10") (pinfunction "SPI_MISO/SD_D0_10") (pintype "passive"))
    )
    (net (code "140") (name "unconnected-(U6-SPI_MOSI{slash}SD_CMD-Pad9)") (class "Default")
      (node (ref "U6") (pin "9") (pinfunction "SPI_MOSI/SD_CMD_9") (pintype "passive"))
    )
  )
)
